# Frequency_Counter.net
KiCad netlist of a schematic drawn in EAGLE
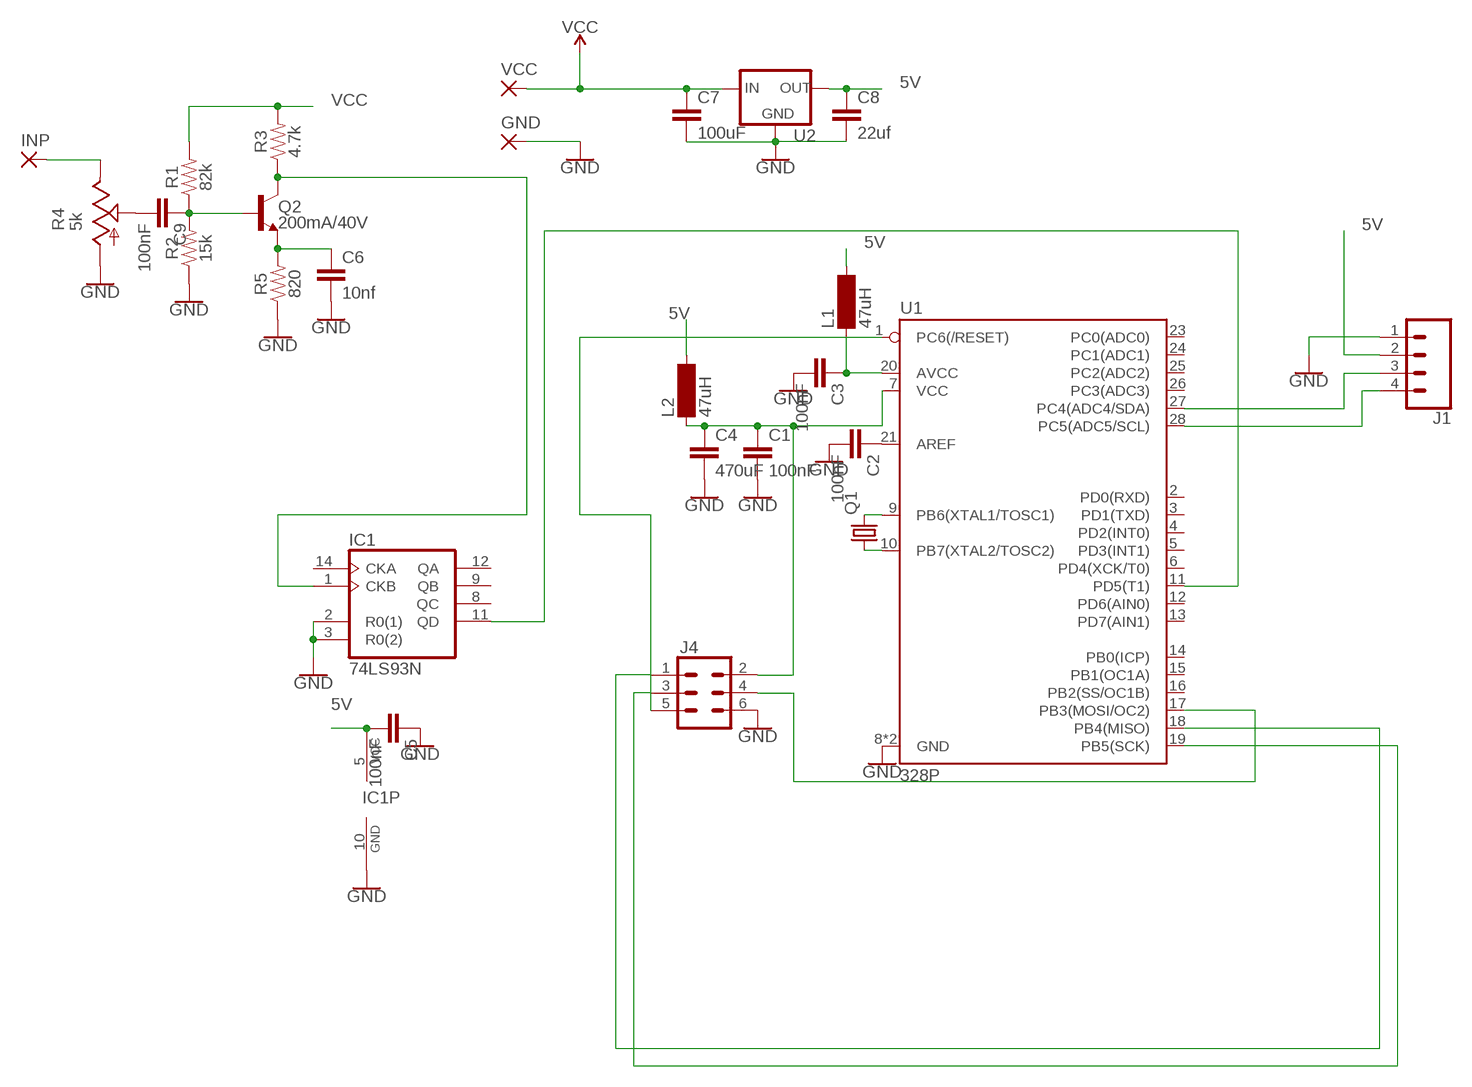
[diagram p0: schematic, sheet 1]

(export (version "E")
  (design (tool "Eeschema 10.0.6"))
  (components
    (comp (ref "C1")
      (value "100nF")
      (footprint "eagle-import:C5B3.5")
      (libsource (lib "eagle-import") (part "C5/3.5"))
    )
    (comp (ref "C2")
      (value "100nF")
      (footprint "eagle-import:C5B3.5")
      (libsource (lib "eagle-import") (part "C5/3.5"))
    )
    (comp (ref "C3")
      (value "100nF")
      (footprint "eagle-import:C5B3.5")
      (libsource (lib "eagle-import") (part "C5/3.5"))
    )
    (comp (ref "C4")
      (value "470uF")
      (footprint "eagle-import:C5B3.5")
      (libsource (lib "eagle-import") (part "C5/3.5"))
    )
    (comp (ref "C5")
      (value "100nF")
      (footprint "eagle-import:C5B3.5")
      (libsource (lib "eagle-import") (part "C5/3.5"))
    )
    (comp (ref "C6")
      (value "10nf")
      (footprint "eagle-import:C5B3.5")
      (libsource (lib "eagle-import") (part "C5/3.5"))
    )
    (comp (ref "C7")
      (value "100uF")
      (footprint "eagle-import:C5B3.5")
      (libsource (lib "eagle-import") (part "C5/3.5"))
    )
    (comp (ref "C8")
      (value "22uf")
      (footprint "eagle-import:C5B3.5")
      (libsource (lib "eagle-import") (part "C5/3.5"))
    )
    (comp (ref "C9")
      (value "100nF")
      (footprint "eagle-import:C5B3.5")
      (libsource (lib "eagle-import") (part "C5/3.5"))
    )
    (comp (ref "GND")
      (value "3,17/1,1")
      (footprint "eagle-import:3,17_1,1")
      (libsource (lib "eagle-import") (part "3,17/1,1"))
    )
    (comp (ref "IC1")
      (value "74LS93N")
      (footprint "eagle-import:DIL14")
      (libsource (lib "eagle-import") (part "7493NLS"))
    )
    (comp (ref "INP")
      (value "2,54/1,1")
      (footprint "eagle-import:2,54_1,1")
      (libsource (lib "eagle-import") (part "2,54/1,1"))
    )
    (comp (ref "J1")
      (value "CONN_04")
      (footprint "eagle-import:1X04")
      (libsource (lib "eagle-import") (part "CONN_04"))
    )
    (comp (ref "J4")
      (value "CONN_03X2NO_SILK")
      (footprint "eagle-import:2X3-NS")
      (libsource (lib "eagle-import") (part "CONN_03X2NO_SILK"))
    )
    (comp (ref "L1")
      (value "47uH")
      (footprint "eagle-import:BS75")
      (libsource (lib "eagle-import") (part "BS75"))
    )
    (comp (ref "L2")
      (value "47uH")
      (footprint "eagle-import:BS75")
      (libsource (lib "eagle-import") (part "BS75"))
    )
    (comp (ref "Q1")
      (value "CRYTALHC49S")
      (footprint "eagle-import:HC49_S")
      (libsource (lib "eagle-import") (part "CRYTALHC49S"))
    )
    (comp (ref "Q2")
      (value "200mA/40V")
      (footprint "eagle-import:TO-92")
      (libsource (lib "eagle-import") (part "TRANS_NPN-2N3904"))
    )
    (comp (ref "R1")
      (value "82k")
      (footprint "eagle-import:AXIAL-0.3")
      (libsource (lib "eagle-import") (part "10KOHM-HORIZ-1/4W-1%"))
    )
    (comp (ref "R2")
      (value "15k")
      (footprint "eagle-import:AXIAL-0.3")
      (libsource (lib "eagle-import") (part "10KOHM-HORIZ-1/4W-1%"))
    )
    (comp (ref "R3")
      (value "4.7k")
      (footprint "eagle-import:AXIAL-0.3")
      (libsource (lib "eagle-import") (part "10KOHM-HORIZ-1/4W-1%"))
    )
    (comp (ref "R4")
      (value "5k")
      (footprint "eagle-import:B25V")
      (libsource (lib "eagle-import") (part "TRIM_US-B25V"))
    )
    (comp (ref "R5")
      (value "820")
      (footprint "eagle-import:AXIAL-0.3")
      (libsource (lib "eagle-import") (part "10KOHM-HORIZ-1/4W-1%"))
    )
    (comp (ref "U1")
      (value "328P")
      (footprint "eagle-import:DIP28")
      (libsource (lib "eagle-import") (part "ATMEGA328P_PDIP"))
    )
    (comp (ref "U2")
      (value "V_REG_78XXSINK")
      (footprint "eagle-import:TO220-IGO")
      (libsource (lib "eagle-import") (part "V_REG_78XXSINK"))
    )
    (comp (ref "VCC")
      (value "3,17/1,1")
      (footprint "eagle-import:3,17_1,1")
      (libsource (lib "eagle-import") (part "3,17/1,1"))
    )
  )
  (nets
    (net (code "1") (name "/5V") (class "Default")
      (node (ref "C5") (pin "2") (pinfunction "2_2") (pintype "passive"))
      (node (ref "C8") (pin "1") (pinfunction "1_1") (pintype "passive"))
      (node (ref "IC1") (pin "5") (pinfunction "VCC_5") (pintype "power_in"))
      (node (ref "J1") (pin "2") (pinfunction "2_2") (pintype "passive"))
      (node (ref "L1") (pin "2") (pinfunction "2_2") (pintype "passive"))
      (node (ref "L2") (pin "2") (pinfunction "2_2") (pintype "passive"))
      (node (ref "U2") (pin "OUT") (pinfunction "OUT_OUT") (pintype "passive"))
    )
    (net (code "2") (name "GND") (class "Default")
      (node (ref "C1") (pin "2") (pinfunction "2_2") (pintype "passive"))
      (node (ref "C2") (pin "2") (pinfunction "2_2") (pintype "passive"))
      (node (ref "C3") (pin "2") (pinfunction "2_2") (pintype "passive"))
      (node (ref "C4") (pin "2") (pinfunction "2_2") (pintype "passive"))
      (node (ref "C5") (pin "1") (pinfunction "1_1") (pintype "passive"))
      (node (ref "C6") (pin "2") (pinfunction "2_2") (pintype "passive"))
      (node (ref "C7") (pin "2") (pinfunction "2_2") (pintype "passive"))
      (node (ref "C8") (pin "2") (pinfunction "2_2") (pintype "passive"))
      (node (ref "GND") (pin "1") (pinfunction "P_1") (pintype "passive"))
      (node (ref "IC1") (pin "10") (pinfunction "GND_10") (pintype "power_in"))
      (node (ref "IC1") (pin "2") (pinfunction "R0(1)_2") (pintype "input"))
      (node (ref "IC1") (pin "3") (pinfunction "R0(2)_3") (pintype "input"))
      (node (ref "J1") (pin "1") (pinfunction "1_1") (pintype "passive"))
      (node (ref "J4") (pin "6") (pinfunction "6_6") (pintype "bidirectional"))
      (node (ref "R2") (pin "P$1") (pinfunction "1_P$1") (pintype "passive"))
      (node (ref "R4") (pin "A") (pinfunction "A_A") (pintype "passive"))
      (node (ref "R5") (pin "P$1") (pinfunction "1_P$1") (pintype "passive"))
      (node (ref "U1") (pin "22") (pinfunction "GND_22") (pintype "bidirectional"))
      (node (ref "U1") (pin "8") (pinfunction "GND_8") (pintype "bidirectional"))
      (node (ref "U2") (pin "GND") (pinfunction "GND_GND") (pintype "input"))
    )
    (net (code "3") (name "Net-(C9-Pad2)") (class "Default")
      (node (ref "C9") (pin "2") (pinfunction "2_2") (pintype "passive"))
      (node (ref "R4") (pin "S") (pinfunction "S_S") (pintype "passive"))
    )
    (net (code "4") (name "Net-(IC1A-CKB)") (class "Default")
      (node (ref "IC1") (pin "1") (pinfunction "CKB_1") (pintype "input"))
      (node (ref "Q2") (pin "3") (pinfunction "C_3") (pintype "passive"))
      (node (ref "R3") (pin "P$1") (pinfunction "1_P$1") (pintype "passive"))
    )
    (net (code "5") (name "Net-(IC1A-QD)") (class "Default")
      (node (ref "IC1") (pin "11") (pinfunction "QD_11") (pintype "output"))
      (node (ref "U1") (pin "11") (pinfunction "PD5(T1)_11") (pintype "bidirectional"))
    )
    (net (code "6") (name "Net-(INP-P)") (class "Default")
      (node (ref "INP") (pin "1") (pinfunction "P_1") (pintype "passive"))
      (node (ref "R4") (pin "E") (pinfunction "E_E") (pintype "passive"))
    )
    (net (code "7") (name "Net-(Q2-B)") (class "Default")
      (node (ref "C9") (pin "1") (pinfunction "1_1") (pintype "passive"))
      (node (ref "Q2") (pin "2") (pinfunction "B_2") (pintype "passive"))
      (node (ref "R1") (pin "P$1") (pinfunction "1_P$1") (pintype "passive"))
      (node (ref "R2") (pin "P$2") (pinfunction "2_P$2") (pintype "passive"))
    )
    (net (code "8") (name "Net-(Q2-E)") (class "Default")
      (node (ref "C6") (pin "1") (pinfunction "1_1") (pintype "passive"))
      (node (ref "Q2") (pin "1") (pinfunction "E_1") (pintype "passive"))
      (node (ref "R5") (pin "P$2") (pinfunction "2_P$2") (pintype "passive"))
    )
    (net (code "9") (name "Net-(U1-AREF)") (class "Default")
      (node (ref "C2") (pin "1") (pinfunction "1_1") (pintype "passive"))
      (node (ref "U1") (pin "21") (pinfunction "AREF_21") (pintype "bidirectional"))
    )
    (net (code "10") (name "Net-(U1-AVCC)") (class "Default")
      (node (ref "C3") (pin "1") (pinfunction "1_1") (pintype "passive"))
      (node (ref "L1") (pin "1") (pinfunction "1_1") (pintype "passive"))
      (node (ref "U1") (pin "20") (pinfunction "AVCC_20") (pintype "bidirectional"))
    )
    (net (code "11") (name "Net-(U1-PB3(MOSI{slash}OC2))") (class "Default")
      (node (ref "J4") (pin "4") (pinfunction "4_4") (pintype "bidirectional"))
      (node (ref "U1") (pin "17") (pinfunction "PB3(MOSI/OC2)_17") (pintype "bidirectional"))
    )
    (net (code "12") (name "Net-(U1-PB4(MISO))") (class "Default")
      (node (ref "J4") (pin "1") (pinfunction "1_1") (pintype "bidirectional"))
      (node (ref "U1") (pin "18") (pinfunction "PB4(MISO)_18") (pintype "bidirectional"))
    )
    (net (code "13") (name "Net-(U1-PB5(SCK))") (class "Default")
      (node (ref "J4") (pin "3") (pinfunction "3_3") (pintype "bidirectional"))
      (node (ref "U1") (pin "19") (pinfunction "PB5(SCK)_19") (pintype "bidirectional"))
    )
    (net (code "14") (name "Net-(U1-PB6(XTAL1{slash}TOSC1))") (class "Default")
      (node (ref "Q1") (pin "2") (pinfunction "2_2") (pintype "passive"))
      (node (ref "U1") (pin "9") (pinfunction "PB6(XTAL1/TOSC1)_9") (pintype "bidirectional"))
    )
    (net (code "15") (name "Net-(U1-PB7(XTAL2{slash}TOSC2))") (class "Default")
      (node (ref "Q1") (pin "1") (pinfunction "1_1") (pintype "passive"))
      (node (ref "U1") (pin "10") (pinfunction "PB7(XTAL2/TOSC2)_10") (pintype "bidirectional"))
    )
    (net (code "16") (name "Net-(U1-PC4(ADC4{slash}SDA))") (class "Default")
      (node (ref "J1") (pin "3") (pinfunction "3_3") (pintype "passive"))
      (node (ref "U1") (pin "27") (pinfunction "PC4(ADC4/SDA)_27") (pintype "bidirectional"))
    )
    (net (code "17") (name "Net-(U1-PC5(ADC5{slash}SCL))") (class "Default")
      (node (ref "J1") (pin "4") (pinfunction "4_4") (pintype "passive"))
      (node (ref "U1") (pin "28") (pinfunction "PC5(ADC5/SCL)_28") (pintype "bidirectional"))
    )
    (net (code "18") (name "Net-(U1-PC6({slash}RESET))") (class "Default")
      (node (ref "J4") (pin "5") (pinfunction "5_5") (pintype "bidirectional"))
      (node (ref "U1") (pin "1") (pinfunction "PC6(/RESET)_1") (pintype "bidirectional"))
    )
    (net (code "19") (name "Net-(U1-VCC)") (class "Default")
      (node (ref "C1") (pin "1") (pinfunction "1_1") (pintype "passive"))
      (node (ref "C4") (pin "1") (pinfunction "1_1") (pintype "passive"))
      (node (ref "J4") (pin "2") (pinfunction "2_2") (pintype "bidirectional"))
      (node (ref "L2") (pin "1") (pinfunction "1_1") (pintype "passive"))
      (node (ref "U1") (pin "7") (pinfunction "VCC_7") (pintype "bidirectional"))
    )
    (net (code "20") (name "VCC") (class "Default")
      (node (ref "C7") (pin "1") (pinfunction "1_1") (pintype "passive"))
      (node (ref "R1") (pin "P$2") (pinfunction "2_P$2") (pintype "passive"))
      (node (ref "R3") (pin "P$2") (pinfunction "2_P$2") (pintype "passive"))
      (node (ref "U2") (pin "IN") (pinfunction "IN_IN") (pintype "input"))
      (node (ref "VCC") (pin "1") (pinfunction "P_1") (pintype "passive"))
    )
    (net (code "21") (name "unconnected-(IC1A-CKA-Pad14)") (class "Default")
      (node (ref "IC1") (pin "14") (pinfunction "CKA_14") (pintype "input"))
    )
    (net (code "22") (name "unconnected-(IC1A-QA-Pad12)") (class "Default")
      (node (ref "IC1") (pin "12") (pinfunction "QA_12") (pintype "output"))
    )
    (net (code "23") (name "unconnected-(IC1A-QB-Pad9)") (class "Default")
      (node (ref "IC1") (pin "9") (pinfunction "QB_9") (pintype "output"))
    )
    (net (code "24") (name "unconnected-(IC1A-QC-Pad8)") (class "Default")
      (node (ref "IC1") (pin "8") (pinfunction "QC_8") (pintype "output"))
    )
    (net (code "25") (name "unconnected-(U1-PB0(ICP)-Pad14)") (class "Default")
      (node (ref "U1") (pin "14") (pinfunction "PB0(ICP)_14") (pintype "bidirectional"))
    )
    (net (code "26") (name "unconnected-(U1-PB1(OC1A)-Pad15)") (class "Default")
      (node (ref "U1") (pin "15") (pinfunction "PB1(OC1A)_15") (pintype "bidirectional"))
    )
    (net (code "27") (name "unconnected-(U1-PB2(SS{slash}OC1B)-Pad16)") (class "Default")
      (node (ref "U1") (pin "16") (pinfunction "PB2(SS/OC1B)_16") (pintype "bidirectional"))
    )
    (net (code "28") (name "unconnected-(U1-PC0(ADC0)-Pad23)") (class "Default")
      (node (ref "U1") (pin "23") (pinfunction "PC0(ADC0)_23") (pintype "bidirectional"))
    )
    (net (code "29") (name "unconnected-(U1-PC1(ADC1)-Pad24)") (class "Default")
      (node (ref "U1") (pin "24") (pinfunction "PC1(ADC1)_24") (pintype "bidirectional"))
    )
    (net (code "30") (name "unconnected-(U1-PC2(ADC2)-Pad25)") (class "Default")
      (node (ref "U1") (pin "25") (pinfunction "PC2(ADC2)_25") (pintype "bidirectional"))
    )
    (net (code "31") (name "unconnected-(U1-PC3(ADC3)-Pad26)") (class "Default")
      (node (ref "U1") (pin "26") (pinfunction "PC3(ADC3)_26") (pintype "bidirectional"))
    )
    (net (code "32") (name "unconnected-(U1-PD0(RXD)-Pad2)") (class "Default")
      (node (ref "U1") (pin "2") (pinfunction "PD0(RXD)_2") (pintype "bidirectional"))
    )
    (net (code "33") (name "unconnected-(U1-PD1(TXD)-Pad3)") (class "Default")
      (node (ref "U1") (pin "3") (pinfunction "PD1(TXD)_3") (pintype "bidirectional"))
    )
    (net (code "34") (name "unconnected-(U1-PD2(INT0)-Pad4)") (class "Default")
      (node (ref "U1") (pin "4") (pinfunction "PD2(INT0)_4") (pintype "bidirectional"))
    )
    (net (code "35") (name "unconnected-(U1-PD3(INT1)-Pad5)") (class "Default")
      (node (ref "U1") (pin "5") (pinfunction "PD3(INT1)_5") (pintype "bidirectional"))
    )
    (net (code "36") (name "unconnected-(U1-PD4(XCK{slash}T0)-Pad6)") (class "Default")
      (node (ref "U1") (pin "6") (pinfunction "PD4(XCK/T0)_6") (pintype "bidirectional"))
    )
    (net (code "37") (name "unconnected-(U1-PD6(AIN0)-Pad12)") (class "Default")
      (node (ref "U1") (pin "12") (pinfunction "PD6(AIN0)_12") (pintype "bidirectional"))
    )
    (net (code "38") (name "unconnected-(U1-PD7(AIN1)-Pad13)") (class "Default")
      (node (ref "U1") (pin "13") (pinfunction "PD7(AIN1)_13") (pintype "bidirectional"))
    )
  )
)
